# Axis.net
KiCad netlist of a schematic drawn in Altium Designer
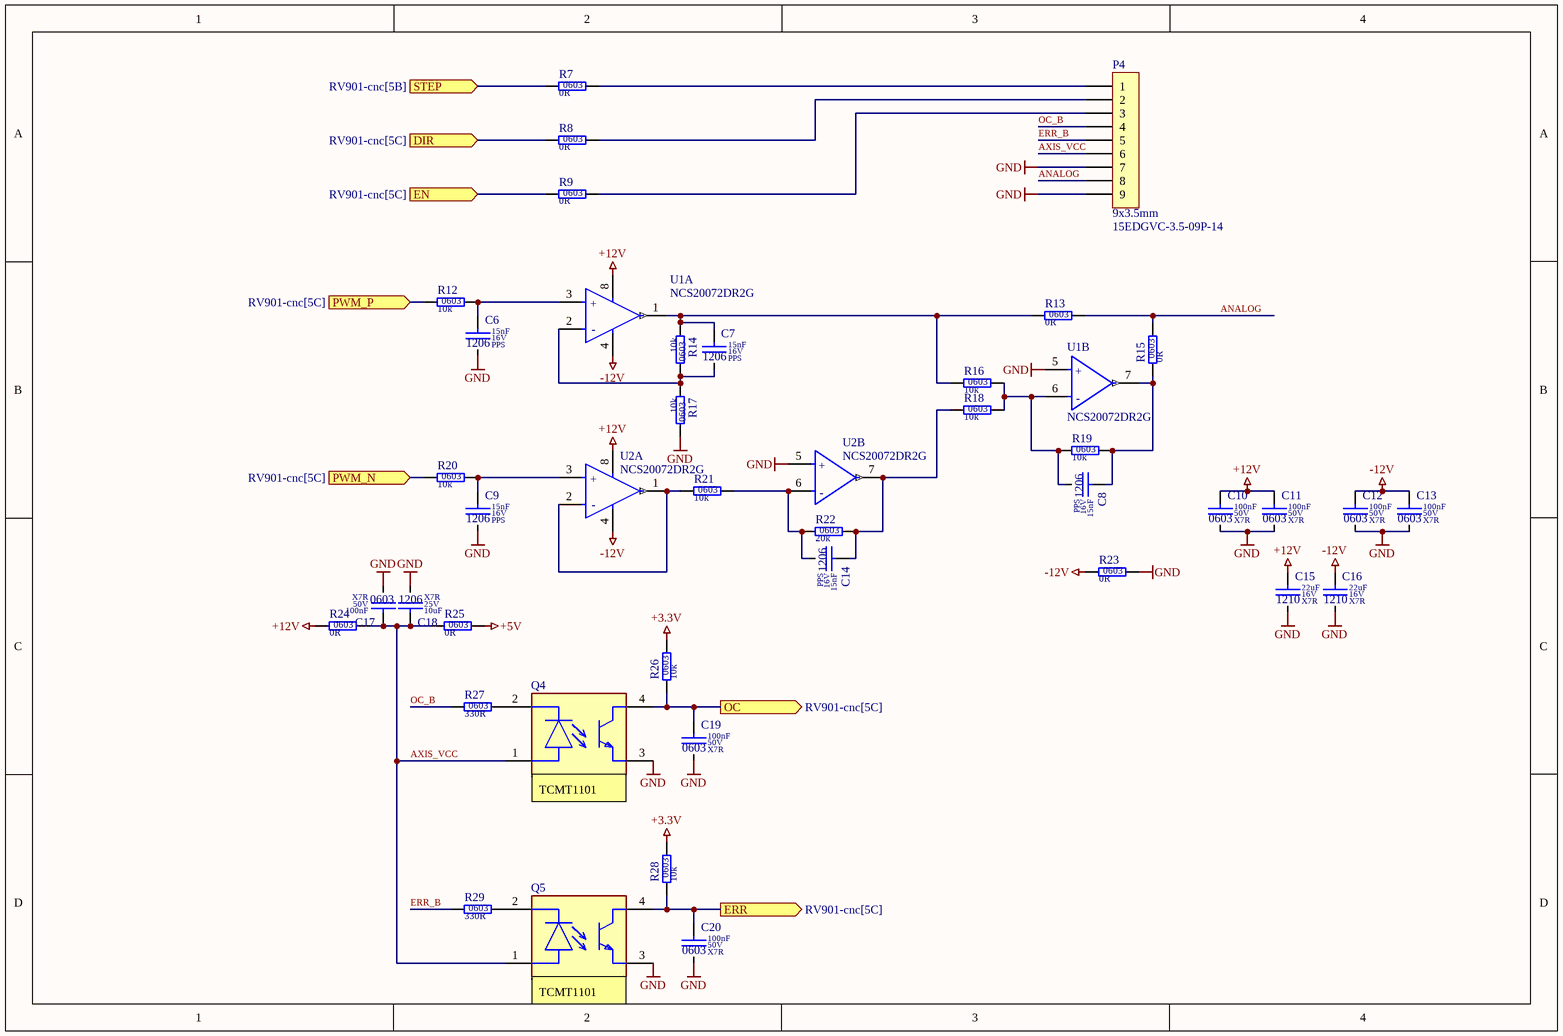
[diagram p0: Axis.SchDoc]

(export (version "E")
  (design (tool "Eeschema 10.0.6"))
  (components
    (comp (ref "C6")
      (value "15nF")
      (footprint "C_1206_3216")
      (description "Capacitor")
      (fields
        (field (name "DIELECTRIC") "PPS")
        (field (name "VOLTAGE") "16V")
        (field (name "SCH_FOOTPRINT") "1206")
        (field (name "PART NUMBER") "C_15nF_16V_PPS_1206_2")
        (field (name "MANUFACTURER") "Panasonic")
      )
      (libsource (lib "Library") (part "C"))
    )
    (comp (ref "C7")
      (value "15nF")
      (footprint "C_1206_3216")
      (description "Capacitor")
      (fields
        (field (name "DIELECTRIC") "PPS")
        (field (name "VOLTAGE") "16V")
        (field (name "SCH_FOOTPRINT") "1206")
        (field (name "PART NUMBER") "C_15nF_16V_PPS_1206_2")
        (field (name "MANUFACTURER") "Panasonic")
      )
      (libsource (lib "Library") (part "C"))
    )
    (comp (ref "C8")
      (value "15nF")
      (footprint "C_1206_3216")
      (description "Capacitor")
      (fields
        (field (name "DIELECTRIC") "PPS")
        (field (name "VOLTAGE") "16V")
        (field (name "SCH_FOOTPRINT") "1206")
        (field (name "PART NUMBER") "C_15nF_16V_PPS_1206_2")
        (field (name "MANUFACTURER") "Panasonic")
      )
      (libsource (lib "Library") (part "C"))
    )
    (comp (ref "C9")
      (value "15nF")
      (footprint "C_1206_3216")
      (description "Capacitor")
      (fields
        (field (name "DIELECTRIC") "PPS")
        (field (name "VOLTAGE") "16V")
        (field (name "SCH_FOOTPRINT") "1206")
        (field (name "PART NUMBER") "C_15nF_16V_PPS_1206_2")
        (field (name "MANUFACTURER") "Panasonic")
      )
      (libsource (lib "Library") (part "C"))
    )
    (comp (ref "C10")
      (value "100nF")
      (footprint "C_0603_1608")
      (description "Capacitor")
      (fields
        (field (name "DIELECTRIC") "X7R")
        (field (name "VOLTAGE") "50V")
        (field (name "SCH_FOOTPRINT") "0603")
        (field (name "PART NUMBER") "C_100nF_50V_X7R_0603_5")
        (field (name "MANUFACTURER") "Samsung")
      )
      (libsource (lib "Library") (part "C"))
    )
    (comp (ref "C11")
      (value "100nF")
      (footprint "C_0603_1608")
      (description "Capacitor")
      (fields
        (field (name "DIELECTRIC") "X7R")
        (field (name "VOLTAGE") "50V")
        (field (name "SCH_FOOTPRINT") "0603")
        (field (name "PART NUMBER") "C_100nF_50V_X7R_0603_5")
        (field (name "MANUFACTURER") "Samsung")
      )
      (libsource (lib "Library") (part "C"))
    )
    (comp (ref "C12")
      (value "100nF")
      (footprint "C_0603_1608")
      (description "Capacitor")
      (fields
        (field (name "DIELECTRIC") "X7R")
        (field (name "VOLTAGE") "50V")
        (field (name "SCH_FOOTPRINT") "0603")
        (field (name "PART NUMBER") "C_100nF_50V_X7R_0603_5")
        (field (name "MANUFACTURER") "Samsung")
      )
      (libsource (lib "Library") (part "C"))
    )
    (comp (ref "C13")
      (value "100nF")
      (footprint "C_0603_1608")
      (description "Capacitor")
      (fields
        (field (name "DIELECTRIC") "X7R")
        (field (name "VOLTAGE") "50V")
        (field (name "SCH_FOOTPRINT") "0603")
        (field (name "PART NUMBER") "C_100nF_50V_X7R_0603_5")
        (field (name "MANUFACTURER") "Samsung")
      )
      (libsource (lib "Library") (part "C"))
    )
    (comp (ref "C14")
      (value "15nF")
      (footprint "C_1206_3216")
      (description "Capacitor")
      (fields
        (field (name "DIELECTRIC") "PPS")
        (field (name "VOLTAGE") "16V")
        (field (name "SCH_FOOTPRINT") "1206")
        (field (name "PART NUMBER") "C_15nF_16V_PPS_1206_2")
        (field (name "MANUFACTURER") "Panasonic")
      )
      (libsource (lib "Library") (part "C"))
    )
    (comp (ref "C15")
      (value "22uF")
      (footprint "C_1210_3225")
      (description "Capacitor")
      (fields
        (field (name "DIELECTRIC") "X7R")
        (field (name "VOLTAGE") "16V")
        (field (name "SCH_FOOTPRINT") "1210")
        (field (name "PART NUMBER") "C_22uF_16V_X7R_1210_10_AECQ1")
        (field (name "MANUFACTURER") "Murata")
      )
      (libsource (lib "Library") (part "C"))
    )
    (comp (ref "C16")
      (value "22uF")
      (footprint "C_1210_3225")
      (description "Capacitor")
      (fields
        (field (name "DIELECTRIC") "X7R")
        (field (name "VOLTAGE") "16V")
        (field (name "SCH_FOOTPRINT") "1210")
        (field (name "PART NUMBER") "C_22uF_16V_X7R_1210_10_AECQ1")
        (field (name "MANUFACTURER") "Murata")
      )
      (libsource (lib "Library") (part "C"))
    )
    (comp (ref "C17")
      (value "100nF")
      (footprint "C_0603_1608")
      (description "Capacitor")
      (fields
        (field (name "DIELECTRIC") "X7R")
        (field (name "VOLTAGE") "50V")
        (field (name "SCH_FOOTPRINT") "0603")
        (field (name "PART NUMBER") "C_100nF_50V_X7R_0603_5")
        (field (name "MANUFACTURER") "Samsung")
      )
      (libsource (lib "Library") (part "C"))
    )
    (comp (ref "C18")
      (value "10uF")
      (footprint "C_1206_3216")
      (description "Capacitor")
      (fields
        (field (name "DIELECTRIC") "X7R")
        (field (name "VOLTAGE") "25V")
        (field (name "SCH_FOOTPRINT") "1206")
        (field (name "PART NUMBER") "C_10uF_25V_X7R_1206_10")
        (field (name "MANUFACTURER") "Samsung")
      )
      (libsource (lib "Library") (part "C"))
    )
    (comp (ref "C19")
      (value "100nF")
      (footprint "C_0603_1608")
      (description "Capacitor")
      (fields
        (field (name "DIELECTRIC") "X7R")
        (field (name "VOLTAGE") "50V")
        (field (name "SCH_FOOTPRINT") "0603")
        (field (name "PART NUMBER") "C_100nF_50V_X7R_0603_5")
        (field (name "MANUFACTURER") "Samsung")
      )
      (libsource (lib "Library") (part "C"))
    )
    (comp (ref "C20")
      (value "100nF")
      (footprint "C_0603_1608")
      (description "Capacitor")
      (fields
        (field (name "DIELECTRIC") "X7R")
        (field (name "VOLTAGE") "50V")
        (field (name "SCH_FOOTPRINT") "0603")
        (field (name "PART NUMBER") "C_100nF_50V_X7R_0603_5")
        (field (name "MANUFACTURER") "Samsung")
      )
      (libsource (lib "Library") (part "C"))
    )
    (comp (ref "P4")
      (value "15EDGVC-3.5-09P-14")
      (footprint "P_15EDGVC-3.5-09P")
      (description "Pin Header")
      (fields
        (field (name "SCH_FOOTPRINT") "9x3.5mm")
        (field (name "PART NUMBER") "P_15EDGVC-3.5-09P-14")
        (field (name "MANUFACTURER") "DEGSON ELECTRONICS")
      )
      (libsource (lib "Library") (part "P_HEADER_1x9"))
    )
    (comp (ref "Q4")
      (value "TCMT1106")
      (footprint "FP-TCMT1106-MFG")
      (fields (field (name "VOLTAGE") "6V"))
      (libsource (lib "Altium Content Vault") (part "e07288ace2826ef443abdfb88e741da"))
    )
    (comp (ref "Q5")
      (value "TCMT1106")
      (footprint "FP-TCMT1106-MFG")
      (fields (field (name "VOLTAGE") "6V"))
      (libsource (lib "Altium Content Vault") (part "e07288ace2826ef443abdfb88e741da"))
    )
    (comp (ref "R7")
      (value "0R")
      (footprint "R_0603_1608")
      (fields
        (field (name "SCH_FOOTPRINT") "0603")
        (field (name "PART NUMBER") "R_0R_0603_1")
        (field (name "VOLTAGE") "75V")
        (field (name "POWER") "100mW")
      )
      (libsource (lib "Library") (part "R"))
    )
    (comp (ref "R8")
      (value "0R")
      (footprint "R_0603_1608")
      (fields
        (field (name "SCH_FOOTPRINT") "0603")
        (field (name "PART NUMBER") "R_0R_0603_1")
        (field (name "VOLTAGE") "75V")
        (field (name "POWER") "100mW")
      )
      (libsource (lib "Library") (part "R"))
    )
    (comp (ref "R9")
      (value "0R")
      (footprint "R_0603_1608")
      (fields
        (field (name "SCH_FOOTPRINT") "0603")
        (field (name "PART NUMBER") "R_0R_0603_1")
        (field (name "VOLTAGE") "75V")
        (field (name "POWER") "100mW")
      )
      (libsource (lib "Library") (part "R"))
    )
    (comp (ref "R12")
      (value "10k")
      (footprint "R_0603_1608")
      (fields
        (field (name "SCH_FOOTPRINT") "0603")
        (field (name "PART NUMBER") "R_10k_0603_1_AECQ0")
        (field (name "VOLTAGE") "75V")
        (field (name "POWER") "100mW")
      )
      (libsource (lib "Library") (part "R"))
    )
    (comp (ref "R13")
      (value "0R")
      (footprint "R_0603_1608")
      (fields
        (field (name "SCH_FOOTPRINT") "0603")
        (field (name "PART NUMBER") "R_0R_0603_1")
        (field (name "VOLTAGE") "75V")
        (field (name "POWER") "100mW")
      )
      (libsource (lib "Library") (part "R"))
    )
    (comp (ref "R14")
      (value "10k")
      (footprint "R_0603_1608")
      (fields
        (field (name "SCH_FOOTPRINT") "0603")
        (field (name "PART NUMBER") "R_10k_0603_1_AECQ0")
        (field (name "VOLTAGE") "75V")
        (field (name "POWER") "100mW")
      )
      (libsource (lib "Library") (part "R"))
    )
    (comp (ref "R15")
      (value "0R")
      (footprint "R_0603_1608")
      (fields
        (field (name "SCH_FOOTPRINT") "0603")
        (field (name "PART NUMBER") "R_0R_0603_1")
        (field (name "VOLTAGE") "75V")
        (field (name "POWER") "100mW")
      )
      (libsource (lib "Library") (part "R"))
    )
    (comp (ref "R16")
      (value "10k")
      (footprint "R_0603_1608")
      (fields
        (field (name "SCH_FOOTPRINT") "0603")
        (field (name "PART NUMBER") "R_10k_0603_1_AECQ0")
        (field (name "VOLTAGE") "75V")
        (field (name "POWER") "100mW")
      )
      (libsource (lib "Library") (part "R"))
    )
    (comp (ref "R17")
      (value "10k")
      (footprint "R_0603_1608")
      (fields
        (field (name "SCH_FOOTPRINT") "0603")
        (field (name "PART NUMBER") "R_10k_0603_1_AECQ0")
        (field (name "VOLTAGE") "75V")
        (field (name "POWER") "100mW")
      )
      (libsource (lib "Library") (part "R"))
    )
    (comp (ref "R18")
      (value "10k")
      (footprint "R_0603_1608")
      (fields
        (field (name "SCH_FOOTPRINT") "0603")
        (field (name "PART NUMBER") "R_10k_0603_1_AECQ0")
        (field (name "VOLTAGE") "75V")
        (field (name "POWER") "100mW")
      )
      (libsource (lib "Library") (part "R"))
    )
    (comp (ref "R19")
      (value "10k")
      (footprint "R_0603_1608")
      (fields
        (field (name "SCH_FOOTPRINT") "0603")
        (field (name "PART NUMBER") "R_10k_0603_1_AECQ0")
        (field (name "VOLTAGE") "75V")
        (field (name "POWER") "100mW")
      )
      (libsource (lib "Library") (part "R"))
    )
    (comp (ref "R20")
      (value "10k")
      (footprint "R_0603_1608")
      (fields
        (field (name "SCH_FOOTPRINT") "0603")
        (field (name "PART NUMBER") "R_10k_0603_1_AECQ0")
        (field (name "VOLTAGE") "75V")
        (field (name "POWER") "100mW")
      )
      (libsource (lib "Library") (part "R"))
    )
    (comp (ref "R21")
      (value "10k")
      (footprint "R_0603_1608")
      (fields
        (field (name "SCH_FOOTPRINT") "0603")
        (field (name "PART NUMBER") "R_10k_0603_1_AECQ0")
        (field (name "VOLTAGE") "75V")
        (field (name "POWER") "100mW")
      )
      (libsource (lib "Library") (part "R"))
    )
    (comp (ref "R22")
      (value "20k")
      (footprint "R_0603_1608")
      (fields
        (field (name "SCH_FOOTPRINT") "0603")
        (field (name "PART NUMBER") "R_20k_0603_1_AECQ0")
        (field (name "VOLTAGE") "75V")
        (field (name "POWER") "100mW")
      )
      (libsource (lib "Library") (part "R"))
    )
    (comp (ref "R23")
      (value "0R")
      (footprint "R_0603_1608")
      (fields
        (field (name "SCH_FOOTPRINT") "0603")
        (field (name "PART NUMBER") "R_0R_0603_1")
        (field (name "VOLTAGE") "75V")
        (field (name "POWER") "100mW")
      )
      (libsource (lib "Library") (part "R"))
    )
    (comp (ref "R24")
      (value "0R")
      (footprint "R_0603_1608")
      (fields
        (field (name "SCH_FOOTPRINT") "0603")
        (field (name "PART NUMBER") "R_0R_0603_1")
        (field (name "VOLTAGE") "75V")
        (field (name "POWER") "100mW")
      )
      (libsource (lib "Library") (part "R"))
    )
    (comp (ref "R25")
      (value "0R")
      (footprint "R_0603_1608")
      (fields
        (field (name "SCH_FOOTPRINT") "0603")
        (field (name "PART NUMBER") "R_0R_0603_1")
        (field (name "VOLTAGE") "75V")
        (field (name "POWER") "100mW")
      )
      (libsource (lib "Library") (part "R"))
    )
    (comp (ref "R26")
      (value "10k")
      (footprint "R_0603_1608")
      (fields
        (field (name "SCH_FOOTPRINT") "0603")
        (field (name "PART NUMBER") "R_10k_0603_1_AECQ0")
        (field (name "VOLTAGE") "75V")
        (field (name "POWER") "100mW")
      )
      (libsource (lib "Library") (part "R"))
    )
    (comp (ref "R27")
      (value "330R")
      (footprint "R_0603_1608")
      (fields
        (field (name "SCH_FOOTPRINT") "0603")
        (field (name "PART NUMBER") "R_330R_0603_1")
        (field (name "VOLTAGE") "50V")
        (field (name "POWER") "100mW")
      )
      (libsource (lib "Library") (part "R"))
    )
    (comp (ref "R28")
      (value "10k")
      (footprint "R_0603_1608")
      (fields
        (field (name "SCH_FOOTPRINT") "0603")
        (field (name "PART NUMBER") "R_10k_0603_1_AECQ0")
        (field (name "VOLTAGE") "75V")
        (field (name "POWER") "100mW")
      )
      (libsource (lib "Library") (part "R"))
    )
    (comp (ref "R29")
      (value "330R")
      (footprint "R_0603_1608")
      (fields
        (field (name "SCH_FOOTPRINT") "0603")
        (field (name "PART NUMBER") "R_330R_0603_1")
        (field (name "VOLTAGE") "50V")
        (field (name "POWER") "100mW")
      )
      (libsource (lib "Library") (part "R"))
    )
    (comp (ref "U1")
      (value "NCS20072DR2G")
      (footprint "FP-751-07-MFG")
      (description "IC OPAMP 3MHZ RRO DUAL 8SOIC")
      (fields
        (field (name "MANUFACTURER") "ON Semiconductor")
        (field (name "OCTOPART") "https://octopart.com/ncs20072dr2g-on+semiconductor-56676507")
      )
      (libsource (lib "Altium Content Vault") (part "b9a7faefb32bdd02b96cd43c2d880af"))
    )
    (comp (ref "U2")
      (value "NCS20072DR2G")
      (footprint "FP-751-07-MFG")
      (description "IC OPAMP 3MHZ RRO DUAL 8SOIC")
      (fields
        (field (name "MANUFACTURER") "ON Semiconductor")
        (field (name "OCTOPART") "https://octopart.com/ncs20072dr2g-on+semiconductor-56676507")
      )
      (libsource (lib "Altium Content Vault") (part "b9a7faefb32bdd02b96cd43c2d880af"))
    )
  )
  (nets
    (net (code "1") (name "+3.3V") (class "Default")
      (node (ref "R26") (pin "2") (pinfunction "2_2") (pintype "passive"))
      (node (ref "R28") (pin "2") (pinfunction "2_2") (pintype "passive"))
    )
    (net (code "2") (name "+5V") (class "Default")
      (node (ref "R25") (pin "2") (pinfunction "2_2") (pintype "passive"))
    )
    (net (code "3") (name "+12V") (class "Default")
      (node (ref "C10") (pin "1") (pinfunction "1_1") (pintype "passive"))
      (node (ref "C11") (pin "1") (pinfunction "1_1") (pintype "passive"))
      (node (ref "C15") (pin "1") (pinfunction "1_1") (pintype "passive"))
      (node (ref "R24") (pin "1") (pinfunction "1_1") (pintype "passive"))
      (node (ref "U1") (pin "8") (pinfunction "VDD_8") (pintype "power_in"))
      (node (ref "U2") (pin "8") (pinfunction "VDD_8") (pintype "power_in"))
    )
    (net (code "4") (name "-12V") (class "Default")
      (node (ref "C12") (pin "1") (pinfunction "1_1") (pintype "passive"))
      (node (ref "C13") (pin "1") (pinfunction "1_1") (pintype "passive"))
      (node (ref "C16") (pin "1") (pinfunction "1_1") (pintype "passive"))
      (node (ref "R23") (pin "1") (pinfunction "1_1") (pintype "passive"))
      (node (ref "U1") (pin "4") (pinfunction "VSS_4") (pintype "power_in"))
      (node (ref "U2") (pin "4") (pinfunction "VSS_4") (pintype "power_in"))
    )
    (net (code "5") (name "/ANALOG") (class "Default")
      (node (ref "P4") (pin "8") (pinfunction "8_8") (pintype "passive"))
      (node (ref "R13") (pin "2") (pinfunction "2_2") (pintype "passive"))
      (node (ref "R15") (pin "2") (pinfunction "2_2") (pintype "passive"))
    )
    (net (code "6") (name "/AXIS_VCC") (class "Default")
      (node (ref "C17") (pin "1") (pinfunction "1_1") (pintype "passive"))
      (node (ref "C18") (pin "1") (pinfunction "1_1") (pintype "passive"))
      (node (ref "P4") (pin "6") (pinfunction "6_6") (pintype "passive"))
      (node (ref "Q4") (pin "1") (pinfunction "A_1") (pintype "passive"))
      (node (ref "Q5") (pin "1") (pinfunction "A_1") (pintype "passive"))
      (node (ref "R24") (pin "2") (pinfunction "2_2") (pintype "passive"))
      (node (ref "R25") (pin "1") (pinfunction "1_1") (pintype "passive"))
    )
    (net (code "7") (name "/DIR") (class "Default")
      (node (ref "R8") (pin "1") (pinfunction "1_1") (pintype "passive"))
    )
    (net (code "8") (name "/EN") (class "Default")
      (node (ref "R9") (pin "1") (pinfunction "1_1") (pintype "passive"))
    )
    (net (code "9") (name "/ERR") (class "Default")
      (node (ref "C20") (pin "1") (pinfunction "1_1") (pintype "passive"))
      (node (ref "Q5") (pin "4") (pinfunction "C_4") (pintype "passive"))
      (node (ref "R28") (pin "1") (pinfunction "1_1") (pintype "passive"))
    )
    (net (code "10") (name "/ERR_B") (class "Default")
      (node (ref "P4") (pin "5") (pinfunction "5_5") (pintype "passive"))
      (node (ref "R29") (pin "1") (pinfunction "1_1") (pintype "passive"))
    )
    (net (code "11") (name "/OC") (class "Default")
      (node (ref "C19") (pin "1") (pinfunction "1_1") (pintype "passive"))
      (node (ref "Q4") (pin "4") (pinfunction "C_4") (pintype "passive"))
      (node (ref "R26") (pin "1") (pinfunction "1_1") (pintype "passive"))
    )
    (net (code "12") (name "/OC_B") (class "Default")
      (node (ref "P4") (pin "4") (pinfunction "4_4") (pintype "passive"))
      (node (ref "R27") (pin "1") (pinfunction "1_1") (pintype "passive"))
    )
    (net (code "13") (name "/PWM_N") (class "Default")
      (node (ref "R20") (pin "1") (pinfunction "1_1") (pintype "passive"))
    )
    (net (code "14") (name "/PWM_P") (class "Default")
      (node (ref "R12") (pin "1") (pinfunction "1_1") (pintype "passive"))
    )
    (net (code "15") (name "/STEP") (class "Default")
      (node (ref "R7") (pin "1") (pinfunction "1_1") (pintype "passive"))
    )
    (net (code "16") (name "GND") (class "Default")
      (node (ref "C10") (pin "2") (pinfunction "2_2") (pintype "passive"))
      (node (ref "C11") (pin "2") (pinfunction "2_2") (pintype "passive"))
      (node (ref "C12") (pin "2") (pinfunction "2_2") (pintype "passive"))
      (node (ref "C13") (pin "2") (pinfunction "2_2") (pintype "passive"))
      (node (ref "C15") (pin "2") (pinfunction "2_2") (pintype "passive"))
      (node (ref "C16") (pin "2") (pinfunction "2_2") (pintype "passive"))
      (node (ref "C17") (pin "2") (pinfunction "2_2") (pintype "passive"))
      (node (ref "C18") (pin "2") (pinfunction "2_2") (pintype "passive"))
      (node (ref "C19") (pin "2") (pinfunction "2_2") (pintype "passive"))
      (node (ref "C20") (pin "2") (pinfunction "2_2") (pintype "passive"))
      (node (ref "C6") (pin "2") (pinfunction "2_2") (pintype "passive"))
      (node (ref "C9") (pin "2") (pinfunction "2_2") (pintype "passive"))
      (node (ref "P4") (pin "7") (pinfunction "7_7") (pintype "passive"))
      (node (ref "P4") (pin "9") (pinfunction "9_9") (pintype "passive"))
      (node (ref "Q4") (pin "3") (pinfunction "E_3") (pintype "passive"))
      (node (ref "Q5") (pin "3") (pinfunction "E_3") (pintype "passive"))
      (node (ref "R17") (pin "2") (pinfunction "2_2") (pintype "passive"))
      (node (ref "R23") (pin "2") (pinfunction "2_2") (pintype "passive"))
      (node (ref "U1") (pin "5") (pinfunction "IN+_2_5") (pintype "tri_state"))
      (node (ref "U2") (pin "5") (pinfunction "IN+_2_5") (pintype "tri_state"))
    )
    (net (code "17") (name "Net-(P4-Pad1)") (class "Default")
      (node (ref "P4") (pin "1") (pinfunction "1_1") (pintype "passive"))
      (node (ref "R7") (pin "2") (pinfunction "2_2") (pintype "passive"))
    )
    (net (code "18") (name "Net-(P4-Pad2)") (class "Default")
      (node (ref "P4") (pin "2") (pinfunction "2_2") (pintype "passive"))
      (node (ref "R8") (pin "2") (pinfunction "2_2") (pintype "passive"))
    )
    (net (code "19") (name "Net-(P4-Pad3)") (class "Default")
      (node (ref "P4") (pin "3") (pinfunction "3_3") (pintype "passive"))
      (node (ref "R9") (pin "2") (pinfunction "2_2") (pintype "passive"))
    )
    (net (code "20") (name "Net-(Q4-C-Pad2)") (class "Default")
      (node (ref "Q4") (pin "2") (pinfunction "C_2") (pintype "passive"))
      (node (ref "R27") (pin "2") (pinfunction "2_2") (pintype "passive"))
    )
    (net (code "21") (name "Net-(Q5-C-Pad2)") (class "Default")
      (node (ref "Q5") (pin "2") (pinfunction "C_2") (pintype "passive"))
      (node (ref "R29") (pin "2") (pinfunction "2_2") (pintype "passive"))
    )
    (net (code "22") (name "Net-(U1A-IN+_1)") (class "Default")
      (node (ref "C6") (pin "1") (pinfunction "1_1") (pintype "passive"))
      (node (ref "R12") (pin "2") (pinfunction "2_2") (pintype "passive"))
      (node (ref "U1") (pin "3") (pinfunction "IN+_1_3") (pintype "tri_state"))
    )
    (net (code "23") (name "Net-(U1A-IN-_1)") (class "Default")
      (node (ref "C7") (pin "2") (pinfunction "2_2") (pintype "passive"))
      (node (ref "R14") (pin "2") (pinfunction "2_2") (pintype "passive"))
      (node (ref "R17") (pin "1") (pinfunction "1_1") (pintype "passive"))
      (node (ref "U1") (pin "2") (pinfunction "IN-_1_2") (pintype "tri_state"))
    )
    (net (code "24") (name "Net-(U1A-OUT_1)") (class "Default")
      (node (ref "C7") (pin "1") (pinfunction "1_1") (pintype "passive"))
      (node (ref "R13") (pin "1") (pinfunction "1_1") (pintype "passive"))
      (node (ref "R14") (pin "1") (pinfunction "1_1") (pintype "passive"))
      (node (ref "R16") (pin "1") (pinfunction "1_1") (pintype "passive"))
      (node (ref "U1") (pin "1") (pinfunction "OUT_1_1") (pintype "output"))
    )
    (net (code "25") (name "Net-(U1B-IN-_2)") (class "Default")
      (node (ref "C8") (pin "2") (pinfunction "2_2") (pintype "passive"))
      (node (ref "R16") (pin "2") (pinfunction "2_2") (pintype "passive"))
      (node (ref "R18") (pin "2") (pinfunction "2_2") (pintype "passive"))
      (node (ref "R19") (pin "1") (pinfunction "1_1") (pintype "passive"))
      (node (ref "U1") (pin "6") (pinfunction "IN-_2_6") (pintype "tri_state"))
    )
    (net (code "26") (name "Net-(U1B-OUT_2)") (class "Default")
      (node (ref "C8") (pin "1") (pinfunction "1_1") (pintype "passive"))
      (node (ref "R15") (pin "1") (pinfunction "1_1") (pintype "passive"))
      (node (ref "R19") (pin "2") (pinfunction "2_2") (pintype "passive"))
      (node (ref "U1") (pin "7") (pinfunction "OUT_2_7") (pintype "output"))
    )
    (net (code "27") (name "Net-(U2A-IN+_1)") (class "Default")
      (node (ref "C9") (pin "1") (pinfunction "1_1") (pintype "passive"))
      (node (ref "R20") (pin "2") (pinfunction "2_2") (pintype "passive"))
      (node (ref "U2") (pin "3") (pinfunction "IN+_1_3") (pintype "tri_state"))
    )
    (net (code "28") (name "Net-(U2A-IN-_1)") (class "Default")
      (node (ref "R21") (pin "1") (pinfunction "1_1") (pintype "passive"))
      (node (ref "U2") (pin "1") (pinfunction "OUT_1_1") (pintype "output"))
      (node (ref "U2") (pin "2") (pinfunction "IN-_1_2") (pintype "tri_state"))
    )
    (net (code "29") (name "Net-(U2B-IN-_2)") (class "Default")
      (node (ref "C14") (pin "2") (pinfunction "2_2") (pintype "passive"))
      (node (ref "R21") (pin "2") (pinfunction "2_2") (pintype "passive"))
      (node (ref "R22") (pin "1") (pinfunction "1_1") (pintype "passive"))
      (node (ref "U2") (pin "6") (pinfunction "IN-_2_6") (pintype "tri_state"))
    )
    (net (code "30") (name "Net-(U2B-OUT_2)") (class "Default")
      (node (ref "C14") (pin "1") (pinfunction "1_1") (pintype "passive"))
      (node (ref "R18") (pin "1") (pinfunction "1_1") (pintype "passive"))
      (node (ref "R22") (pin "2") (pinfunction "2_2") (pintype "passive"))
      (node (ref "U2") (pin "7") (pinfunction "OUT_2_7") (pintype "output"))
    )
  )
)
